# Retro_Audio_Rev2_1.net
KiCad netlist of a schematic drawn in EAGLE
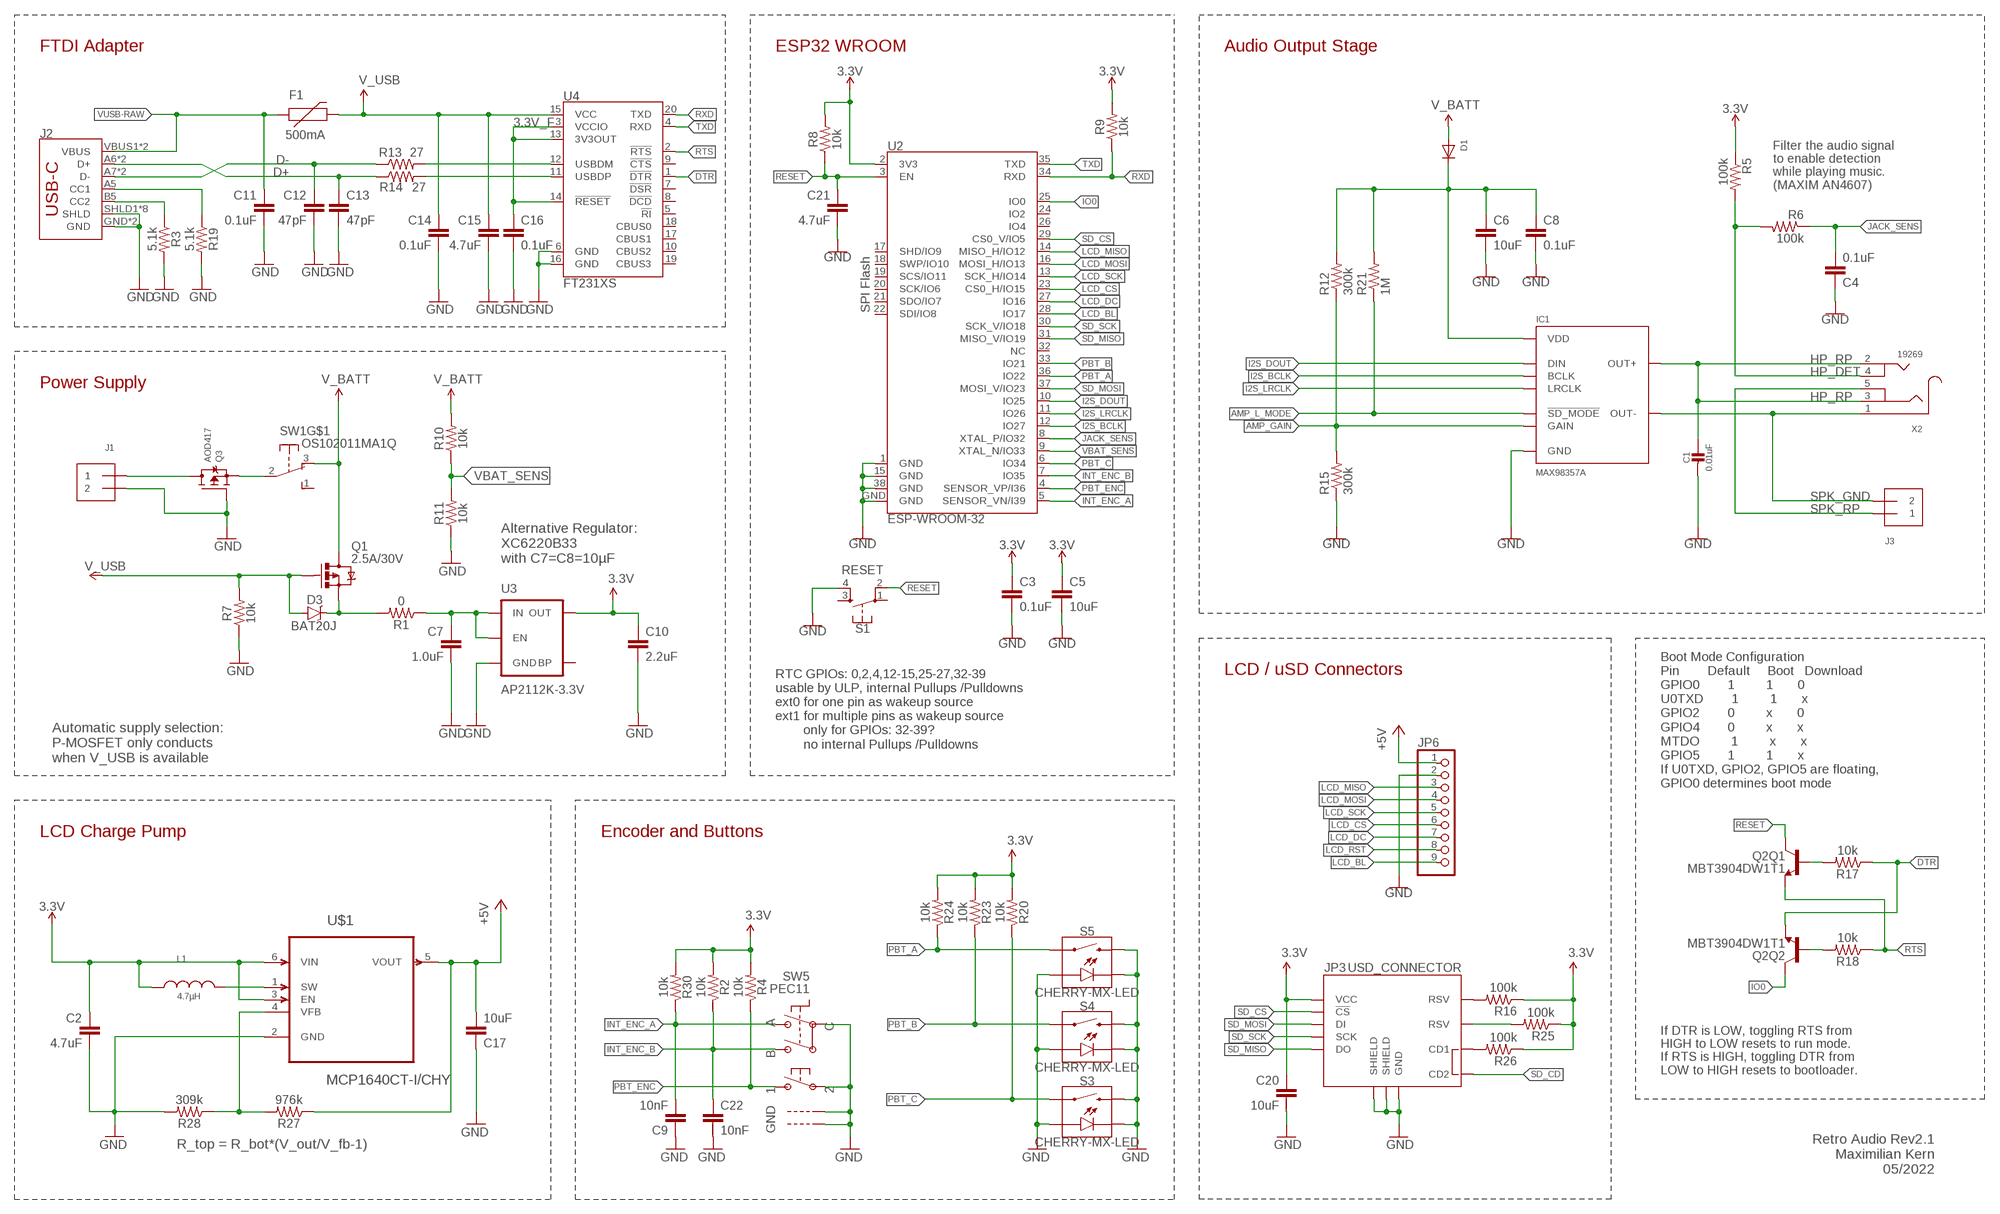
[diagram p0: schematic, sheet 1]

(export (version "E")
  (design (tool "Eeschema 10.0.6"))
  (components
    (comp (ref "C1")
      (value "0.01uF")
      (footprint "eagle-import:0603-NO")
      (libsource (lib "eagle-import") (part "CAP_CERAMIC0603_NO"))
    )
    (comp (ref "C2")
      (value "4.7uF")
      (footprint "eagle-import:0603-CAP")
      (libsource (lib "eagle-import") (part "4.7UF-6.3V-10%(0603)0603"))
    )
    (comp (ref "C3")
      (value "0.1uF")
      (footprint "eagle-import:0603")
      (libsource (lib "eagle-import") (part "0.1UF-0603-25V-(+80/-20%)"))
    )
    (comp (ref "C4")
      (value "0.1uF")
      (footprint "eagle-import:0603")
      (libsource (lib "eagle-import") (part "0.1UF-0603-25V-(+80/-20%)"))
    )
    (comp (ref "C5")
      (value "10uF")
      (footprint "eagle-import:0603")
      (libsource (lib "eagle-import") (part "10UF-0603-6.3V-20%"))
    )
    (comp (ref "C6")
      (value "10uF")
      (footprint "eagle-import:0603")
      (libsource (lib "eagle-import") (part "10UF-0603-6.3V-20%"))
    )
    (comp (ref "C7")
      (value "1.0uF")
      (footprint "eagle-import:0805")
      (libsource (lib "eagle-import") (part "1.0UF-0805-25V-(+80/-20%)"))
    )
    (comp (ref "C8")
      (value "0.1uF")
      (footprint "eagle-import:0603")
      (libsource (lib "eagle-import") (part "0.1UF-0603-25V-(+80/-20%)"))
    )
    (comp (ref "C9")
      (value "10nF")
      (footprint "eagle-import:0805")
      (libsource (lib "eagle-import") (part "1.0UF-0805-25V-(+80/-20%)"))
    )
    (comp (ref "C10")
      (value "2.2uF")
      (footprint "eagle-import:0805")
      (libsource (lib "eagle-import") (part "1.0UF-0805-25V-(+80/-20%)"))
    )
    (comp (ref "C11")
      (value "0.1uF")
      (footprint "eagle-import:0603")
      (libsource (lib "eagle-import") (part "0.1UF-0603-25V-(+80/-20%)"))
    )
    (comp (ref "C12")
      (value "47pF")
      (footprint "eagle-import:0603")
      (libsource (lib "eagle-import") (part "47PF-0603-50V-5%"))
    )
    (comp (ref "C13")
      (value "47pF")
      (footprint "eagle-import:0603")
      (libsource (lib "eagle-import") (part "47PF-0603-50V-5%"))
    )
    (comp (ref "C14")
      (value "0.1uF")
      (footprint "eagle-import:0603")
      (libsource (lib "eagle-import") (part "0.1UF-0603-25V-(+80/-20%)"))
    )
    (comp (ref "C15")
      (value "4.7uF")
      (footprint "eagle-import:0603-CAP")
      (libsource (lib "eagle-import") (part "4.7UF-6.3V-10%(0603)0603"))
    )
    (comp (ref "C16")
      (value "0.1uF")
      (footprint "eagle-import:0603")
      (libsource (lib "eagle-import") (part "0.1UF-0603-25V-(+80/-20%)"))
    )
    (comp (ref "C17")
      (value "10uF")
      (footprint "eagle-import:0603")
      (libsource (lib "eagle-import") (part "47PF-0603-50V-5%"))
    )
    (comp (ref "C20")
      (value "10uF")
      (footprint "eagle-import:0603")
      (libsource (lib "eagle-import") (part "10UF-0603-6.3V-20%"))
    )
    (comp (ref "C21")
      (value "4.7uF")
      (footprint "eagle-import:0603-CAP")
      (libsource (lib "eagle-import") (part "4.7UF-6.3V-10%(0603)0603"))
    )
    (comp (ref "C22")
      (value "10nF")
      (footprint "eagle-import:0805")
      (libsource (lib "eagle-import") (part "1.0UF-0805-25V-(+80/-20%)"))
    )
    (comp (ref "D1")
      (value "DIODE_SOD-123FL")
      (footprint "eagle-import:SOD-123FL")
      (libsource (lib "eagle-import") (part "DIODE_SOD-123FL"))
    )
    (comp (ref "D3")
      (value "BAT20J")
      (footprint "eagle-import:SOD-323")
      (libsource (lib "eagle-import") (part "DIODE-SCHOTTKY-BAT20J"))
    )
    (comp (ref "F1")
      (value "500mA")
      (footprint "eagle-import:PTC-1206")
      (libsource (lib "eagle-import") (part "PTCSMD"))
    )
    (comp (ref "IC1")
      (value "MAX98357A")
      (footprint "eagle-import:TQFN-16")
      (libsource (lib "eagle-import") (part "MAX98357A"))
    )
    (comp (ref "J1")
      (value "TERMBLOCK_1X2")
      (footprint "eagle-import:TERMBLOCK_1X2-3.5MM")
      (libsource (lib "eagle-import") (part "TERMBLOCK_1X2"))
    )
    (comp (ref "J2")
      (value "USB_C16PIN")
      (footprint "eagle-import:USB-C-16P")
      (libsource (lib "eagle-import") (part "USB_C16PIN"))
    )
    (comp (ref "J3")
      (value "TERMBLOCK_1X2")
      (footprint "eagle-import:TERMBLOCK_1X2-3.5MM")
      (libsource (lib "eagle-import") (part "TERMBLOCK_1X2"))
    )
    (comp (ref "JP3")
      (value "USD_CONNECTOR")
      (footprint "eagle-import:MICRO-SD-SOCKET-PP")
      (libsource (lib "eagle-import") (part "USD_CONNECTOR"))
    )
    (comp (ref "JP6")
      (value "PINHD-1X9")
      (footprint "eagle-import:1X09")
      (libsource (lib "eagle-import") (part "PINHD-1X9"))
    )
    (comp (ref "L1")
      (value "4.7µH")
      (footprint "eagle-import:WE-TPC_2811_2813_OLD")
      (libsource (lib "eagle-import") (part "WE-TPC_2813_744029004"))
    )
    (comp (ref "Q1")
      (value "2.5A/30V")
      (footprint "eagle-import:SOT23-3")
      (libsource (lib "eagle-import") (part "MOSFET-PCHANNELDMG2307L"))
    )
    (comp (ref "Q2")
      (value "MBT3904DW1T1")
      (footprint "eagle-import:SC70-6")
      (libsource (lib "eagle-import") (part "MBT3904DW1T1"))
    )
    (comp (ref "Q3")
      (value "AOD417")
      (footprint "eagle-import:TO252")
      (libsource (lib "eagle-import") (part "MOSFET-PTO252"))
    )
    (comp (ref "R1")
      (value "0")
      (footprint "eagle-import:0603")
      (libsource (lib "eagle-import") (part "10KOHM-0603-1/10W-1%"))
    )
    (comp (ref "R2")
      (value "10k")
      (footprint "eagle-import:0603")
      (libsource (lib "eagle-import") (part "10KOHM-0603-1/10W-1%"))
    )
    (comp (ref "R3")
      (value "5.1k")
      (footprint "eagle-import:0603")
      (libsource (lib "eagle-import") (part "10KOHM-0603-1/10W-1%"))
    )
    (comp (ref "R4")
      (value "10k")
      (footprint "eagle-import:0603")
      (libsource (lib "eagle-import") (part "10KOHM-0603-1/10W-1%"))
    )
    (comp (ref "R5")
      (value "100k")
      (footprint "eagle-import:R0603")
      (libsource (lib "eagle-import") (part "R-US_R0603"))
    )
    (comp (ref "R6")
      (value "100k")
      (footprint "eagle-import:R0603")
      (libsource (lib "eagle-import") (part "R-US_R0603"))
    )
    (comp (ref "R7")
      (value "10k")
      (footprint "eagle-import:0603")
      (libsource (lib "eagle-import") (part "10KOHM-0603-1/10W-1%"))
    )
    (comp (ref "R8")
      (value "10k")
      (footprint "eagle-import:0603")
      (libsource (lib "eagle-import") (part "10KOHM-0603-1/10W-1%"))
    )
    (comp (ref "R9")
      (value "10k")
      (footprint "eagle-import:0603")
      (libsource (lib "eagle-import") (part "10KOHM-0603-1/10W-1%"))
    )
    (comp (ref "R10")
      (value "10k")
      (footprint "eagle-import:0603")
      (libsource (lib "eagle-import") (part "10KOHM-0603-1/10W-1%"))
    )
    (comp (ref "R11")
      (value "10k")
      (footprint "eagle-import:0603")
      (libsource (lib "eagle-import") (part "10KOHM-0603-1/10W-1%"))
    )
    (comp (ref "R12")
      (value "300k")
      (footprint "eagle-import:R0603")
      (libsource (lib "eagle-import") (part "R-US_R0603"))
    )
    (comp (ref "R13")
      (value "27")
      (footprint "eagle-import:0603")
      (libsource (lib "eagle-import") (part "27OHM1/10W1%(0603)0603-RES"))
    )
    (comp (ref "R14")
      (value "27")
      (footprint "eagle-import:0603")
      (libsource (lib "eagle-import") (part "27OHM1/10W1%(0603)0603-RES"))
    )
    (comp (ref "R15")
      (value "300k")
      (footprint "eagle-import:R0603")
      (libsource (lib "eagle-import") (part "R-US_R0603"))
    )
    (comp (ref "R16")
      (value "100k")
      (footprint "eagle-import:R0603")
      (libsource (lib "eagle-import") (part "R-US_R0603"))
    )
    (comp (ref "R17")
      (value "10k")
      (footprint "eagle-import:0603")
      (libsource (lib "eagle-import") (part "10KOHM-0603-1/10W-1%"))
    )
    (comp (ref "R18")
      (value "10k")
      (footprint "eagle-import:0603")
      (libsource (lib "eagle-import") (part "10KOHM-0603-1/10W-1%"))
    )
    (comp (ref "R19")
      (value "5.1k")
      (footprint "eagle-import:0603")
      (libsource (lib "eagle-import") (part "10KOHM-0603-1/10W-1%"))
    )
    (comp (ref "R20")
      (value "10k")
      (footprint "eagle-import:0603")
      (libsource (lib "eagle-import") (part "10KOHM-0603-1/10W-1%"))
    )
    (comp (ref "R21")
      (value "1M")
      (footprint "eagle-import:R0603")
      (libsource (lib "eagle-import") (part "R-US_R0603"))
    )
    (comp (ref "R23")
      (value "10k")
      (footprint "eagle-import:0603")
      (libsource (lib "eagle-import") (part "10KOHM-0603-1/10W-1%"))
    )
    (comp (ref "R24")
      (value "10k")
      (footprint "eagle-import:0603")
      (libsource (lib "eagle-import") (part "10KOHM-0603-1/10W-1%"))
    )
    (comp (ref "R25")
      (value "100k")
      (footprint "eagle-import:R0603")
      (libsource (lib "eagle-import") (part "R-US_R0603"))
    )
    (comp (ref "R26")
      (value "100k")
      (footprint "eagle-import:R0603")
      (libsource (lib "eagle-import") (part "R-US_R0603"))
    )
    (comp (ref "R27")
      (value "976k")
      (footprint "eagle-import:0603")
      (libsource (lib "eagle-import") (part "10KOHM-0603-1/10W-1%"))
    )
    (comp (ref "R28")
      (value "309k")
      (footprint "eagle-import:0603")
      (libsource (lib "eagle-import") (part "10KOHM-0603-1/10W-1%"))
    )
    (comp (ref "R30")
      (value "10k")
      (footprint "eagle-import:0603")
      (libsource (lib "eagle-import") (part "10KOHM-0603-1/10W-1%"))
    )
    (comp (ref "S1")
      (value "RESET")
      (footprint "eagle-import:TACTILE_SWITCH_SMD_4.6X2.8MM")
      (libsource (lib "eagle-import") (part "MOMENTARY-SWITCH-SPST-2-SMD-4.6X2.8MM"))
    )
    (comp (ref "S3")
      (value "CHERRY-MX-LED")
      (footprint "eagle-import:CHERRY-MX-LED")
      (libsource (lib "eagle-import") (part "CHERRY-MX-LED"))
    )
    (comp (ref "S4")
      (value "CHERRY-MX-LED")
      (footprint "eagle-import:CHERRY-MX-LED")
      (libsource (lib "eagle-import") (part "CHERRY-MX-LED"))
    )
    (comp (ref "S5")
      (value "CHERRY-MX-LED")
      (footprint "eagle-import:CHERRY-MX-LED")
      (libsource (lib "eagle-import") (part "CHERRY-MX-LED"))
    )
    (comp (ref "SW1")
      (value "OS102011MA1Q")
      (footprint "eagle-import:OS102011MA1Q")
      (libsource (lib "eagle-import") (part "OS102011MA1Q"))
    )
    (comp (ref "SW5")
      (value "PEC11")
      (footprint "eagle-import:PEC11+SWITCH")
      (libsource (lib "eagle-import") (part "ENCODER_PLUS_SWITCH_PEC11_BOURNS"))
    )
    (comp (ref "U$1")
      (value "MCP1640CT-I/CHY")
      (footprint "eagle-import:SOT95P270X145-6N")
      (libsource (lib "eagle-import") (part "MCP1640CT-I/CHY"))
    )
    (comp (ref "U2")
      (value "ESP-WROOM-32")
      (footprint "eagle-import:ESP-WROOM-32")
      (libsource (lib "eagle-import") (part "ESP-WROOM-32"))
    )
    (comp (ref "U3")
      (value "AP2112K-3.3V")
      (footprint "eagle-import:SOT23-5")
      (libsource (lib "eagle-import") (part "V_REG_LDOSMD"))
    )
    (comp (ref "U4")
      (value "FT231XS")
      (footprint "eagle-import:SSOP20_L")
      (libsource (lib "eagle-import") (part "FT231XS"))
    )
    (comp (ref "X2")
      (value "19269")
      (footprint "eagle-import:4UCONN_19269")
      (libsource (lib "eagle-import") (part "AUDIO_3.5MMJACK"))
    )
  )
  (nets
    (net (code "1") (name "+5V") (class "Default")
      (node (ref "C17") (pin "2") (pinfunction "2_2") (pintype "passive"))
      (node (ref "JP6") (pin "1") (pinfunction "1_1") (pintype "passive"))
      (node (ref "R27") (pin "1") (pinfunction "1_1") (pintype "passive"))
      (node (ref "U$1") (pin "5") (pinfunction "VOUT_5") (pintype "output"))
    )
    (net (code "2") (name "/3.3V_F") (class "Default")
      (node (ref "C16") (pin "1") (pinfunction "1_1") (pintype "passive"))
      (node (ref "U4") (pin "13") (pinfunction "3V3OUT_13") (pintype "bidirectional"))
      (node (ref "U4") (pin "14") (pinfunction "~{RESET}_14") (pintype "bidirectional"))
      (node (ref "U4") (pin "3") (pinfunction "VCCIO_3") (pintype "bidirectional"))
    )
    (net (code "3") (name "/D+") (class "Default")
      (node (ref "C13") (pin "1") (pinfunction "1_1") (pintype "passive"))
      (node (ref "J2") (pin "A6") (pinfunction "D+_A6") (pintype "bidirectional"))
      (node (ref "J2") (pin "B6") (pinfunction "D+_B6") (pintype "bidirectional"))
      (node (ref "R14") (pin "1") (pinfunction "1_1") (pintype "passive"))
    )
    (net (code "4") (name "/D-") (class "Default")
      (node (ref "C12") (pin "1") (pinfunction "1_1") (pintype "passive"))
      (node (ref "J2") (pin "A7") (pinfunction "D-_A7") (pintype "bidirectional"))
      (node (ref "J2") (pin "B7") (pinfunction "D-_B7") (pintype "bidirectional"))
      (node (ref "R13") (pin "1") (pinfunction "1_1") (pintype "passive"))
    )
    (net (code "5") (name "/HP_DET") (class "Default")
      (node (ref "R5") (pin "2") (pinfunction "2_2") (pintype "passive"))
      (node (ref "R6") (pin "2") (pinfunction "2_2") (pintype "passive"))
      (node (ref "X2") (pin "4") (pinfunction "P$4_4") (pintype "bidirectional"))
    )
    (net (code "6") (name "/HP_RP") (class "Default")
      (node (ref "C1") (pin "1") (pinfunction "1_1") (pintype "passive"))
      (node (ref "IC1") (pin "P$9") (pinfunction "OUT+_P$9") (pintype "bidirectional"))
      (node (ref "X2") (pin "2") (pinfunction "P$5_2") (pintype "bidirectional"))
      (node (ref "X2") (pin "3") (pinfunction "P$2_3") (pintype "bidirectional"))
    )
    (net (code "7") (name "/SPK_GND") (class "Default")
      (node (ref "IC1") (pin "P$10") (pinfunction "OUT-_P$10") (pintype "bidirectional"))
      (node (ref "J3") (pin "2") (pinfunction "2_2") (pintype "passive"))
      (node (ref "X2") (pin "1") (pinfunction "P$1_1") (pintype "bidirectional"))
    )
    (net (code "8") (name "/SPK_RP") (class "Default")
      (node (ref "J3") (pin "1") (pinfunction "1_1") (pintype "passive"))
      (node (ref "X2") (pin "5") (pinfunction "P$3_5") (pintype "bidirectional"))
    )
    (net (code "9") (name "3.3V") (class "Default")
      (node (ref "C10") (pin "1") (pinfunction "1_1") (pintype "passive"))
      (node (ref "C2") (pin "1") (pinfunction "1_1") (pintype "passive"))
      (node (ref "C20") (pin "1") (pinfunction "1_1") (pintype "passive"))
      (node (ref "C3") (pin "1") (pinfunction "1_1") (pintype "passive"))
      (node (ref "C5") (pin "1") (pinfunction "1_1") (pintype "passive"))
      (node (ref "JP3") (pin "VCC") (pinfunction "VCC_VCC") (pintype "bidirectional"))
      (node (ref "L1") (pin "1") (pinfunction "1_1") (pintype "passive"))
      (node (ref "R16") (pin "1") (pinfunction "1_1") (pintype "passive"))
      (node (ref "R2") (pin "2") (pinfunction "2_2") (pintype "passive"))
      (node (ref "R20") (pin "2") (pinfunction "2_2") (pintype "passive"))
      (node (ref "R23") (pin "2") (pinfunction "2_2") (pintype "passive"))
      (node (ref "R24") (pin "2") (pinfunction "2_2") (pintype "passive"))
      (node (ref "R25") (pin "1") (pinfunction "1_1") (pintype "passive"))
      (node (ref "R26") (pin "1") (pinfunction "1_1") (pintype "passive"))
      (node (ref "R30") (pin "2") (pinfunction "2_2") (pintype "passive"))
      (node (ref "R4") (pin "2") (pinfunction "2_2") (pintype "passive"))
      (node (ref "R5") (pin "1") (pinfunction "1_1") (pintype "passive"))
      (node (ref "R8") (pin "2") (pinfunction "2_2") (pintype "passive"))
      (node (ref "R9") (pin "2") (pinfunction "2_2") (pintype "passive"))
      (node (ref "U$1") (pin "3") (pinfunction "EN_3") (pintype "input"))
      (node (ref "U$1") (pin "6") (pinfunction "VIN_6") (pintype "input"))
      (node (ref "U2") (pin "2") (pinfunction "3V3_2") (pintype "bidirectional"))
      (node (ref "U3") (pin "5") (pinfunction "OUT_5") (pintype "passive"))
    )
    (net (code "10") (name "AMP_GAIN") (class "Default")
      (node (ref "IC1") (pin "P$2") (pinfunction "GAIN_P$2") (pintype "bidirectional"))
      (node (ref "R12") (pin "1") (pinfunction "1_1") (pintype "passive"))
      (node (ref "R15") (pin "2") (pinfunction "2_2") (pintype "passive"))
    )
    (net (code "11") (name "AMP_L_MODE") (class "Default")
      (node (ref "IC1") (pin "P$4") (pinfunction "~{SD_MODE}_P$4") (pintype "bidirectional"))
      (node (ref "R21") (pin "1") (pinfunction "1_1") (pintype "passive"))
    )
    (net (code "12") (name "DTR") (class "Default")
      (node (ref "Q2") (pin "1") (pinfunction "E_1") (pintype "passive"))
      (node (ref "R17") (pin "1") (pinfunction "1_1") (pintype "passive"))
      (node (ref "U4") (pin "1") (pinfunction "~{DTR}_1") (pintype "bidirectional"))
    )
    (net (code "13") (name "GND") (class "Default")
      (node (ref "C1") (pin "2") (pinfunction "2_2") (pintype "passive"))
      (node (ref "C10") (pin "2") (pinfunction "2_2") (pintype "passive"))
      (node (ref "C11") (pin "2") (pinfunction "2_2") (pintype "passive"))
      (node (ref "C12") (pin "2") (pinfunction "2_2") (pintype "passive"))
      (node (ref "C13") (pin "2") (pinfunction "2_2") (pintype "passive"))
      (node (ref "C14") (pin "2") (pinfunction "2_2") (pintype "passive"))
      (node (ref "C15") (pin "2") (pinfunction "2_2") (pintype "passive"))
      (node (ref "C16") (pin "2") (pinfunction "2_2") (pintype "passive"))
      (node (ref "C17") (pin "1") (pinfunction "1_1") (pintype "passive"))
      (node (ref "C2") (pin "2") (pinfunction "2_2") (pintype "passive"))
      (node (ref "C20") (pin "2") (pinfunction "2_2") (pintype "passive"))
      (node (ref "C21") (pin "2") (pinfunction "2_2") (pintype "passive"))
      (node (ref "C22") (pin "2") (pinfunction "2_2") (pintype "passive"))
      (node (ref "C3") (pin "2") (pinfunction "2_2") (pintype "passive"))
      (node (ref "C4") (pin "1") (pinfunction "1_1") (pintype "passive"))
      (node (ref "C5") (pin "2") (pinfunction "2_2") (pintype "passive"))
      (node (ref "C6") (pin "2") (pinfunction "2_2") (pintype "passive"))
      (node (ref "C7") (pin "2") (pinfunction "2_2") (pintype "passive"))
      (node (ref "C8") (pin "2") (pinfunction "2_2") (pintype "passive"))
      (node (ref "C9") (pin "1") (pinfunction "1_1") (pintype "passive"))
      (node (ref "IC1") (pin "P$11") (pinfunction "GND_P$11") (pintype "bidirectional"))
      (node (ref "IC1") (pin "P$15") (pinfunction "GND_P$15") (pintype "bidirectional"))
      (node (ref "IC1") (pin "P$3") (pinfunction "GND_P$3") (pintype "bidirectional"))
      (node (ref "IC1") (pin "P$EP") (pinfunction "GND_P$EP") (pintype "bidirectional"))
      (node (ref "J1") (pin "2") (pinfunction "2_2") (pintype "passive"))
      (node (ref "J2") (pin "GND") (pinfunction "GND_GND") (pintype "bidirectional"))
      (node (ref "J2") (pin "GND2") (pinfunction "GND_GND2") (pintype "bidirectional"))
      (node (ref "J2") (pin "SHLD1") (pinfunction "SHLD_SHLD1") (pintype "bidirectional"))
      (node (ref "J2") (pin "SHLD2") (pinfunction "SHLD_SHLD2") (pintype "bidirectional"))
      (node (ref "J2") (pin "SHLD3") (pinfunction "SHLD_SHLD3") (pintype "bidirectional"))
      (node (ref "J2") (pin "SHLD4") (pinfunction "SHLD_SHLD4") (pintype "bidirectional"))
      (node (ref "J2") (pin "SHLD5") (pinfunction "SHLD_SHLD5") (pintype "bidirectional"))
      (node (ref "J2") (pin "SHLD6") (pinfunction "SHLD_SHLD6") (pintype "bidirectional"))
      (node (ref "J2") (pin "SHLD7") (pinfunction "SHLD_SHLD7") (pintype "bidirectional"))
      (node (ref "J2") (pin "SHLD8") (pinfunction "SHLD_SHLD8") (pintype "bidirectional"))
      (node (ref "JP3") (pin "GND") (pinfunction "GND_GND") (pintype "bidirectional"))
      (node (ref "JP3") (pin "GND1") (pinfunction "SHIELD_GND1") (pintype "bidirectional"))
      (node (ref "JP3") (pin "GND3") (pinfunction "SHIELD_GND3") (pintype "bidirectional"))
      (node (ref "JP6") (pin "2") (pinfunction "2_2") (pintype "passive"))
      (node (ref "Q3") (pin "1") (pinfunction "G_1") (pintype "passive"))
      (node (ref "R11") (pin "1") (pinfunction "1_1") (pintype "passive"))
      (node (ref "R15") (pin "1") (pinfunction "1_1") (pintype "passive"))
      (node (ref "R19") (pin "2") (pinfunction "2_2") (pintype "passive"))
      (node (ref "R28") (pin "2") (pinfunction "2_2") (pintype "passive"))
      (node (ref "R3") (pin "2") (pinfunction "2_2") (pintype "passive"))
      (node (ref "R7") (pin "1") (pinfunction "1_1") (pintype "passive"))
      (node (ref "S1") (pin "4") (pinfunction "4_4") (pintype "passive"))
      (node (ref "S3") (pin "A") (pinfunction "A_A") (pintype "passive"))
      (node (ref "S3") (pin "K") (pinfunction "C_K") (pintype "passive"))
      (node (ref "S3") (pin "S2") (pinfunction "S2_S2") (pintype "passive"))
      (node (ref "S4") (pin "A") (pinfunction "A_A") (pintype "passive"))
      (node (ref "S4") (pin "K") (pinfunction "C_K") (pintype "passive"))
      (node (ref "S4") (pin "S2") (pinfunction "S2_S2") (pintype "passive"))
      (node (ref "S5") (pin "A") (pinfunction "A_A") (pintype "passive"))
      (node (ref "S5") (pin "K") (pinfunction "C_K") (pintype "passive"))
      (node (ref "S5") (pin "S2") (pinfunction "S2_S2") (pintype "passive"))
      (node (ref "SW5") (pin "P$2") (pinfunction "P$2_P$2") (pintype "passive"))
      (node (ref "SW5") (pin "P$C") (pinfunction "P$C_P$C") (pintype "passive"))
      (node (ref "SW5") (pin "P$GND1") (pinfunction "P$GND1_P$GND1") (pintype "passive"))
      (node (ref "SW5") (pin "P$GND2") (pinfunction "P$GND2_P$GND2") (pintype "passive"))
      (node (ref "U$1") (pin "2") (pinfunction "GND_2") (pintype "passive"))
      (node (ref "U2") (pin "1") (pinfunction "GND_1") (pintype "bidirectional"))
      (node (ref "U2") (pin "15") (pinfunction "GND_15") (pintype "bidirectional"))
      (node (ref "U2") (pin "38") (pinfunction "GND_38") (pintype "bidirectional"))
      (node (ref "U2") (pin "GND") (pinfunction "GND_GND") (pintype "bidirectional"))
      (node (ref "U3") (pin "2") (pinfunction "GND_2") (pintype "input"))
      (node (ref "U4") (pin "16") (pinfunction "GND_16") (pintype "bidirectional"))
      (node (ref "U4") (pin "6") (pinfunction "GND_6") (pintype "bidirectional"))
    )
    (net (code "14") (name "I2S_BCLK") (class "Default")
      (node (ref "IC1") (pin "P$16") (pinfunction "BCLK_P$16") (pintype "bidirectional"))
      (node (ref "U2") (pin "12") (pinfunction "IO27_12") (pintype "bidirectional"))
    )
    (net (code "15") (name "I2S_DOUT") (class "Default")
      (node (ref "IC1") (pin "P$1") (pinfunction "DIN_P$1") (pintype "bidirectional"))
      (node (ref "U2") (pin "10") (pinfunction "IO25_10") (pintype "bidirectional"))
    )
    (net (code "16") (name "I2S_LRCLK") (class "Default")
      (node (ref "IC1") (pin "P$14") (pinfunction "LRCLK_P$14") (pintype "bidirectional"))
      (node (ref "U2") (pin "11") (pinfunction "IO26_11") (pintype "bidirectional"))
    )
    (net (code "17") (name "INT_ENC_A") (class "Default")
      (node (ref "C9") (pin "2") (pinfunction "2_2") (pintype "passive"))
      (node (ref "R30") (pin "1") (pinfunction "1_1") (pintype "passive"))
      (node (ref "SW5") (pin "P$A") (pinfunction "P$A_P$A") (pintype "passive"))
      (node (ref "U2") (pin "5") (pinfunction "SENSOR_VN/I39_5") (pintype "bidirectional"))
    )
    (net (code "18") (name "INT_ENC_B") (class "Default")
      (node (ref "C22") (pin "1") (pinfunction "1_1") (pintype "passive"))
      (node (ref "R2") (pin "1") (pinfunction "1_1") (pintype "passive"))
      (node (ref "SW5") (pin "P$B") (pinfunction "P$B_P$B") (pintype "passive"))
      (node (ref "U2") (pin "7") (pinfunction "IO35_7") (pintype "bidirectional"))
    )
    (net (code "19") (name "IO0") (class "Default")
      (node (ref "Q2") (pin "6") (pinfunction "C_6") (pintype "passive"))
      (node (ref "U2") (pin "25") (pinfunction "IO0_25") (pintype "bidirectional"))
    )
    (net (code "20") (name "JACK_SENS") (class "Default")
      (node (ref "C4") (pin "2") (pinfunction "2_2") (pintype "passive"))
      (node (ref "R6") (pin "1") (pinfunction "1_1") (pintype "passive"))
      (node (ref "U2") (pin "8") (pinfunction "XTAL_P/IO32_8") (pintype "bidirectional"))
    )
    (net (code "21") (name "LCD_BL") (class "Default")
      (node (ref "JP6") (pin "9") (pinfunction "9_9") (pintype "passive"))
      (node (ref "U2") (pin "28") (pinfunction "IO17_28") (pintype "bidirectional"))
    )
    (net (code "22") (name "LCD_CS") (class "Default")
      (node (ref "JP6") (pin "6") (pinfunction "6_6") (pintype "passive"))
      (node (ref "U2") (pin "23") (pinfunction "CS0_H/IO15_23") (pintype "bidirectional"))
    )
    (net (code "23") (name "LCD_DC") (class "Default")
      (node (ref "JP6") (pin "7") (pinfunction "7_7") (pintype "passive"))
      (node (ref "U2") (pin "27") (pinfunction "IO16_27") (pintype "bidirectional"))
    )
    (net (code "24") (name "LCD_MISO") (class "Default")
      (node (ref "JP6") (pin "3") (pinfunction "3_3") (pintype "passive"))
      (node (ref "U2") (pin "14") (pinfunction "MISO_H/IO12_14") (pintype "bidirectional"))
    )
    (net (code "25") (name "LCD_MOSI") (class "Default")
      (node (ref "JP6") (pin "4") (pinfunction "4_4") (pintype "passive"))
      (node (ref "U2") (pin "16") (pinfunction "MOSI_H/IO13_16") (pintype "bidirectional"))
    )
    (net (code "26") (name "LCD_RST") (class "Default")
      (node (ref "JP6") (pin "8") (pinfunction "8_8") (pintype "passive"))
    )
    (net (code "27") (name "LCD_SCK") (class "Default")
      (node (ref "JP6") (pin "5") (pinfunction "5_5") (pintype "passive"))
      (node (ref "U2") (pin "13") (pinfunction "SCK_H/IO14_13") (pintype "bidirectional"))
    )
    (net (code "28") (name "Net-(C6-Pad1)") (class "Default")
      (node (ref "C6") (pin "1") (pinfunction "1_1") (pintype "passive"))
      (node (ref "C8") (pin "1") (pinfunction "1_1") (pintype "passive"))
      (node (ref "D1") (pin "C") (pinfunction "C_C") (pintype "passive"))
      (node (ref "IC1") (pin "P$7") (pinfunction "VDD_P$7") (pintype "bidirectional"))
      (node (ref "IC1") (pin "P$8") (pinfunction "VDD_P$8") (pintype "bidirectional"))
      (node (ref "R12") (pin "2") (pinfunction "2_2") (pintype "passive"))
      (node (ref "R21") (pin "2") (pinfunction "2_2") (pintype "passive"))
    )
    (net (code "29") (name "Net-(J2-CC1)") (class "Default")
      (node (ref "J2") (pin "A5") (pinfunction "CC1_A5") (pintype "bidirectional"))
      (node (ref "R19") (pin "1") (pinfunction "1_1") (pintype "passive"))
    )
    (net (code "30") (name "Net-(J2-CC2)") (class "Default")
      (node (ref "J2") (pin "B5") (pinfunction "CC2_B5") (pintype "bidirectional"))
      (node (ref "R3") (pin "1") (pinfunction "1_1") (pintype "passive"))
    )
    (net (code "31") (name "Net-(JP3-PadCD1)") (class "Default")
      (node (ref "JP3") (pin "CD1") (pinfunction "CD1_CD1") (pintype "bidirectional"))
      (node (ref "R26") (pin "2") (pinfunction "2_2") (pintype "passive"))
    )
    (net (code "32") (name "Net-(JP3-RSV-PadRSV1)") (class "Default")
      (node (ref "JP3") (pin "RSV1") (pinfunction "RSV_RSV1") (pintype "bidirectional"))
      (node (ref "R16") (pin "2") (pinfunction "2_2") (pintype "passive"))
    )
    (net (code "33") (name "Net-(JP3-RSV-PadRSV2)") (class "Default")
      (node (ref "JP3") (pin "RSV2") (pinfunction "RSV_RSV2") (pintype "bidirectional"))
      (node (ref "R25") (pin "2") (pinfunction "2_2") (pintype "passive"))
    )
    (net (code "34") (name "Net-(Q1-S)") (class "Default")
      (node (ref "D3") (pin "C") (pinfunction "C_C") (pintype "passive"))
      (node (ref "Q1") (pin "2") (pinfunction "S_2") (pintype "passive"))
      (node (ref "R1") (pin "2") (pinfunction "2_2") (pintype "passive"))
    )
    (net (code "35") (name "Net-(Q2A-B)") (class "Default")
      (node (ref "Q2") (pin "5") (pinfunction "B_5") (pintype "passive"))
      (node (ref "R17") (pin "2") (pinfunction "2_2") (pintype "passive"))
    )
    (net (code "36") (name "Net-(Q2B-B)") (class "Default")
      (node (ref "Q2") (pin "2") (pinfunction "B_2") (pintype "passive"))
      (node (ref "R18") (pin "2") (pinfunction "2_2") (pintype "passive"))
    )
    (net (code "37") (name "Net-(Q3-D)") (class "Default")
      (node (ref "J1") (pin "1") (pinfunction "1_1") (pintype "passive"))
      (node (ref "Q3") (pin "3") (pinfunction "D_3") (pintype "passive"))
    )
    (net (code "38") (name "Net-(Q3-S)") (class "Default")
      (node (ref "Q3") (pin "2") (pinfunction "S_2") (pintype "passive"))
      (node (ref "SW1") (pin "2") (pinfunction "P_2") (pintype "passive"))
    )
    (net (code "39") (name "Net-(U$1-SW)") (class "Default")
      (node (ref "L1") (pin "2") (pinfunction "2_2") (pintype "passive"))
      (node (ref "U$1") (pin "1") (pinfunction "SW_1") (pintype "input"))
    )
    (net (code "40") (name "Net-(U$1-VFB)") (class "Default")
      (node (ref "R27") (pin "2") (pinfunction "2_2") (pintype "passive"))
      (node (ref "R28") (pin "1") (pinfunction "1_1") (pintype "passive"))
      (node (ref "U$1") (pin "4") (pinfunction "VFB_4") (pintype "input"))
    )
    (net (code "41") (name "Net-(U3-EN)") (class "Default")
      (node (ref "C7") (pin "1") (pinfunction "1_1") (pintype "passive"))
      (node (ref "R1") (pin "1") (pinfunction "1_1") (pintype "passive"))
      (node (ref "U3") (pin "1") (pinfunction "IN_1") (pintype "input"))
      (node (ref "U3") (pin "3") (pinfunction "EN_3") (pintype "input"))
    )
    (net (code "42") (name "Net-(U4-USBDM)") (class "Default")
      (node (ref "R13") (pin "2") (pinfunction "2_2") (pintype "passive"))
      (node (ref "U4") (pin "12") (pinfunction "USBDM_12") (pintype "bidirectional"))
    )
    (net (code "43") (name "Net-(U4-USBDP)") (class "Default")
      (node (ref "R14") (pin "2") (pinfunction "2_2") (pintype "passive"))
      (node (ref "U4") (pin "11") (pinfunction "USBDP_11") (pintype "bidirectional"))
    )
    (net (code "44") (name "PBT_A") (class "Default")
      (node (ref "R24") (pin "1") (pinfunction "1_1") (pintype "passive"))
      (node (ref "S5") (pin "S1") (pinfunction "S1_S1") (pintype "passive"))
      (node (ref "U2") (pin "36") (pinfunction "IO22_36") (pintype "bidirectional"))
    )
    (net (code "45") (name "PBT_B") (class "Default")
      (node (ref "R23") (pin "1") (pinfunction "1_1") (pintype "passive"))
      (node (ref "S4") (pin "S1") (pinfunction "S1_S1") (pintype "passive"))
      (node (ref "U2") (pin "33") (pinfunction "IO21_33") (pintype "bidirectional"))
    )
    (net (code "46") (name "PBT_C") (class "Default")
      (node (ref "R20") (pin "1") (pinfunction "1_1") (pintype "passive"))
      (node (ref "S3") (pin "S1") (pinfunction "S1_S1") (pintype "passive"))
      (node (ref "U2") (pin "6") (pinfunction "IO34_6") (pintype "bidirectional"))
    )
    (net (code "47") (name "PBT_ENC") (class "Default")
      (node (ref "R4") (pin "1") (pinfunction "1_1") (pintype "passive"))
      (node (ref "SW5") (pin "P$1") (pinfunction "P$1_P$1") (pintype "passive"))
      (node (ref "U2") (pin "4") (pinfunction "SENSOR_VP/I36_4") (pintype "bidirectional"))
    )
    (net (code "48") (name "RESET") (class "Default")
      (node (ref "C21") (pin "1") (pinfunction "1_1") (pintype "passive"))
      (node (ref "Q2") (pin "3") (pinfunction "C_3") (pintype "passive"))
      (node (ref "R8") (pin "1") (pinfunction "1_1") (pintype "passive"))
      (node (ref "S1") (pin "2") (pinfunction "2_2") (pintype "passive"))
      (node (ref "U2") (pin "3") (pinfunction "EN_3") (pintype "bidirectional"))
    )
    (net (code "49") (name "RTS") (class "Default")
      (node (ref "Q2") (pin "4") (pinfunction "E_4") (pintype "passive"))
      (node (ref "R18") (pin "1") (pinfunction "1_1") (pintype "passive"))
      (node (ref "U4") (pin "2") (pinfunction "~{RTS}_2") (pintype "bidirectional"))
    )
    (net (code "50") (name "RXD") (class "Default")
      (node (ref "R9") (pin "1") (pinfunction "1_1") (pintype "passive"))
      (node (ref "U2") (pin "34") (pinfunction "RXD_34") (pintype "bidirectional"))
      (node (ref "U4") (pin "20") (pinfunction "TXD_20") (pintype "bidirectional"))
    )
    (net (code "51") (name "SD_CD") (class "Default")
      (node (ref "JP3") (pin "CD2") (pinfunction "CD2_CD2") (pintype "bidirectional"))
    )
    (net (code "52") (name "SD_CS") (class "Default")
      (node (ref "JP3") (pin "CS") (pinfunction "~{CS}_CS") (pintype "bidirectional"))
      (node (ref "U2") (pin "29") (pinfunction "CS0_V/IO5_29") (pintype "bidirectional"))
    )
    (net (code "53") (name "SD_MISO") (class "Default")
      (node (ref "JP3") (pin "DO") (pinfunction "DO_DO") (pintype "bidirectional"))
      (node (ref "U2") (pin "31") (pinfunction "MISO_V/IO19_31") (pintype "bidirectional"))
    )
    (net (code "54") (name "SD_MOSI") (class "Default")
      (node (ref "JP3") (pin "DI") (pinfunction "DI_DI") (pintype "bidirectional"))
      (node (ref "U2") (pin "37") (pinfunction "MOSI_V/IO23_37") (pintype "bidirectional"))
    )
    (net (code "55") (name "SD_SCK") (class "Default")
      (node (ref "JP3") (pin "SCLK") (pinfunction "SCK_SCLK") (pintype "bidirectional"))
      (node (ref "U2") (pin "30") (pinfunction "SCK_V/IO18_30") (pintype "bidirectional"))
    )
    (net (code "56") (name "TXD") (class "Default")
      (node (ref "U2") (pin "35") (pinfunction "TXD_35") (pintype "bidirectional"))
      (node (ref "U4") (pin "4") (pinfunction "RXD_4") (pintype "bidirectional"))
    )
    (net (code "57") (name "VBAT_SENS") (class "Default")
      (node (ref "R10") (pin "1") (pinfunction "1_1") (pintype "passive"))
      (node (ref "R11") (pin "2") (pinfunction "2_2") (pintype "passive"))
      (node (ref "U2") (pin "9") (pinfunction "XTAL_N/IO33_9") (pintype "bidirectional"))
    )
    (net (code "58") (name "VUSB-RAW") (class "Default")
      (node (ref "C11") (pin "1") (pinfunction "1_1") (pintype "passive"))
      (node (ref "F1") (pin "1") (pinfunction "1_1") (pintype "bidirectional"))
      (node (ref "J2") (pin "VBUS1") (pinfunction "VBUS_VBUS1") (pintype "bidirectional"))
      (node (ref "J2") (pin "VBUS2") (pinfunction "VBUS_VBUS2") (pintype "bidirectional"))
    )
    (net (code "59") (name "V_BATT") (class "Default")
      (node (ref "D1") (pin "A") (pinfunction "A_A") (pintype "passive"))
      (node (ref "Q1") (pin "3") (pinfunction "D_3") (pintype "passive"))
      (node (ref "R10") (pin "2") (pinfunction "2_2") (pintype "passive"))
      (node (ref "SW1") (pin "3") (pinfunction "O_3") (pintype "passive"))
    )
    (net (code "60") (name "V_USB") (class "Default")
      (node (ref "C14") (pin "1") (pinfunction "1_1") (pintype "passive"))
      (node (ref "C15") (pin "1") (pinfunction "1_1") (pintype "passive"))
      (node (ref "D3") (pin "A") (pinfunction "A_A") (pintype "passive"))
      (node (ref "F1") (pin "2") (pinfunction "2_2") (pintype "bidirectional"))
      (node (ref "Q1") (pin "1") (pinfunction "G_1") (pintype "passive"))
      (node (ref "R7") (pin "2") (pinfunction "2_2") (pintype "passive"))
      (node (ref "U4") (pin "15") (pinfunction "VCC_15") (pintype "bidirectional"))
    )
    (net (code "61") (name "unconnected-(S1-Pad1)") (class "Default")
      (node (ref "S1") (pin "1") (pinfunction "1_1") (pintype "passive"))
    )
    (net (code "62") (name "unconnected-(S1-Pad3)") (class "Default")
      (node (ref "S1") (pin "3") (pinfunction "3_3") (pintype "passive"))
    )
    (net (code "63") (name "unconnected-(SW1A-S-Pad1)") (class "Default")
      (node (ref "SW1") (pin "1") (pinfunction "S_1") (pintype "passive"))
    )
    (net (code "64") (name "unconnected-(U2-IO2-Pad24)") (class "Default")
      (node (ref "U2") (pin "24") (pinfunction "IO2_24") (pintype "bidirectional"))
    )
    (net (code "65") (name "unconnected-(U2-IO4-Pad26)") (class "Default")
      (node (ref "U2") (pin "26") (pinfunction "IO4_26") (pintype "bidirectional"))
    )
    (net (code "66") (name "unconnected-(U2-NC-Pad32)") (class "Default")
      (node (ref "U2") (pin "32") (pinfunction "NC_32") (pintype "bidirectional"))
    )
    (net (code "67") (name "unconnected-(U2-SCK{slash}IO6-Pad20)") (class "Default")
      (node (ref "U2") (pin "20") (pinfunction "SCK/IO6_20") (pintype "bidirectional"))
    )
    (net (code "68") (name "unconnected-(U2-SCS{slash}IO11-Pad19)") (class "Default")
      (node (ref "U2") (pin "19") (pinfunction "SCS/IO11_19") (pintype "bidirectional"))
    )
    (net (code "69") (name "unconnected-(U2-SDI{slash}IO8-Pad22)") (class "Default")
      (node (ref "U2") (pin "22") (pinfunction "SDI/IO8_22") (pintype "bidirectional"))
    )
    (net (code "70") (name "unconnected-(U2-SDO{slash}IO7-Pad21)") (class "Default")
      (node (ref "U2") (pin "21") (pinfunction "SDO/IO7_21") (pintype "bidirectional"))
    )
    (net (code "71") (name "unconnected-(U2-SHD{slash}IO9-Pad17)") (class "Default")
      (node (ref "U2") (pin "17") (pinfunction "SHD/IO9_17") (pintype "bidirectional"))
    )
    (net (code "72") (name "unconnected-(U2-SWP{slash}IO10-Pad18)") (class "Default")
      (node (ref "U2") (pin "18") (pinfunction "SWP/IO10_18") (pintype "bidirectional"))
    )
    (net (code "73") (name "unconnected-(U3-BP-Pad4)") (class "Default")
      (node (ref "U3") (pin "4") (pinfunction "BP_4") (pintype "input"))
    )
    (net (code "74") (name "unconnected-(U4-CBUS0-Pad18)") (class "Default")
      (node (ref "U4") (pin "18") (pinfunction "CBUS0_18") (pintype "bidirectional"))
    )
    (net (code "75") (name "unconnected-(U4-CBUS1-Pad17)") (class "Default")
      (node (ref "U4") (pin "17") (pinfunction "CBUS1_17") (pintype "bidirectional"))
    )
    (net (code "76") (name "unconnected-(U4-CBUS2-Pad10)") (class "Default")
      (node (ref "U4") (pin "10") (pinfunction "CBUS2_10") (pintype "bidirectional"))
    )
    (net (code "77") (name "unconnected-(U4-CBUS3-Pad19)") (class "Default")
      (node (ref "U4") (pin "19") (pinfunction "CBUS3_19") (pintype "bidirectional"))
    )
    (net (code "78") (name "unconnected-(U4-~{CTS}-Pad9)") (class "Default")
      (node (ref "U4") (pin "9") (pinfunction "~{CTS}_9") (pintype "bidirectional"))
    )
    (net (code "79") (name "unconnected-(U4-~{DCD}-Pad8)") (class "Default")
      (node (ref "U4") (pin "8") (pinfunction "~{DCD}_8") (pintype "bidirectional"))
    )
    (net (code "80") (name "unconnected-(U4-~{DSR}-Pad7)") (class "Default")
      (node (ref "U4") (pin "7") (pinfunction "~{DSR}_7") (pintype "bidirectional"))
    )
    (net (code "81") (name "unconnected-(U4-~{RI}-Pad5)") (class "Default")
      (node (ref "U4") (pin "5") (pinfunction "~{RI}_5") (pintype "bidirectional"))
    )
  )
)
